# Sensors.net
KiCad netlist of a schematic drawn in Altium Designer
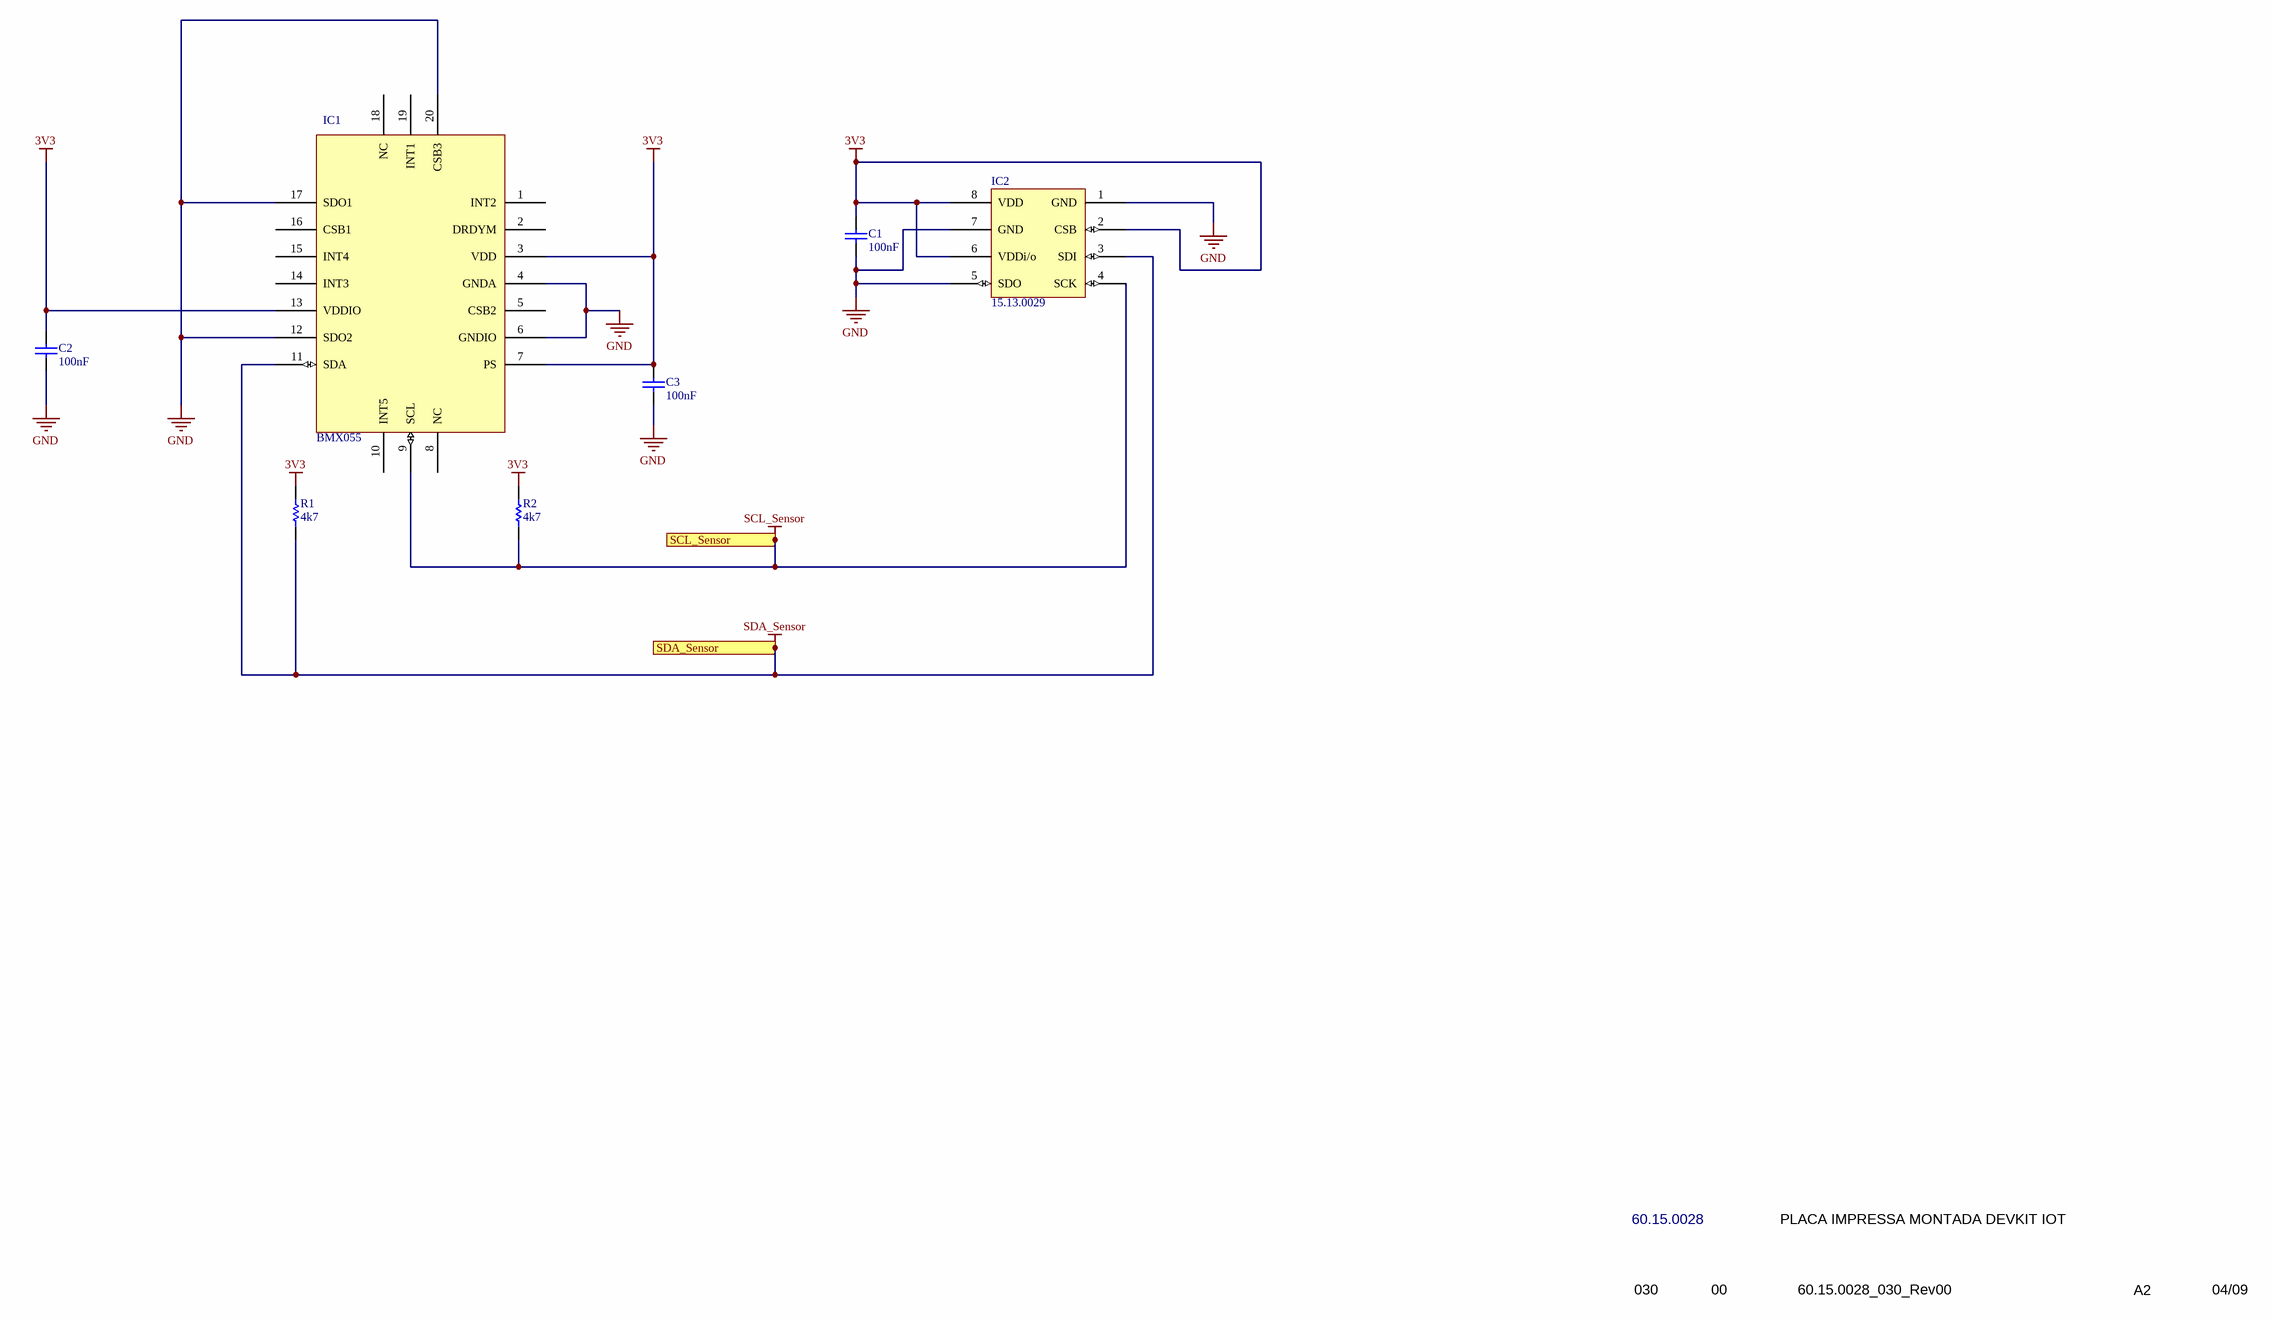
[diagram p0: Sensors.SchDoc]

(export (version "E")
  (design (tool "Eeschema 10.0.6"))
  (components
    (comp (ref "C1")
      (value "16.23.0333")
      (footprint "16.23.0333")
      (description "CC 100NF 16V X5R 0402 SMD")
      (fields (field (name "ALTIUM_UNNAMED_1") "100nF"))
      (libsource (lib "OMNI-CAPACITORES") (part "16.23.0333"))
    )
    (comp (ref "C2")
      (value "16.23.0333")
      (footprint "16.23.0333")
      (description "CC 100NF 16V X5R 0402 SMD")
      (fields (field (name "ALTIUM_UNNAMED_1") "100nF"))
      (libsource (lib "OMNI-CAPACITORES") (part "16.23.0333"))
    )
    (comp (ref "C3")
      (value "16.23.0333")
      (footprint "16.23.0333")
      (description "CC 100NF 16V X5R 0402 SMD")
      (fields (field (name "ALTIUM_UNNAMED_1") "100nF"))
      (libsource (lib "OMNI-CAPACITORES") (part "16.23.0333"))
    )
    (comp (ref "IC1")
      (value "BMX055")
      (footprint "15.15.0010")
      (description "SENSOR ACELEROMETRO MAGNETOMETRO E GIROSCOPIO - BMX055")
      (libsource (lib "OMNI-SENSORES") (part "15.15.0010"))
    )
    (comp (ref "IC2")
      (value "15.13.0029")
      (footprint "15.13.0029")
      (description "SENSOR DE TEMPERATURA UMIDADE E PRESSAO - BME280")
      (libsource (lib "OMNI-SENSORES") (part "15.13.0029"))
    )
    (comp (ref "R1")
      (value "4k7")
      (footprint "66.24.0659")
      (description "RES MET 0,1W 4,7K OHMS 1% 100 PPM 50 V SMD 0603 PBF")
      (fields (field (name "Comment") "66.24.0659"))
      (libsource (lib "OMNI-RESISTORES") (part "66.24.0659"))
    )
    (comp (ref "R2")
      (value "4k7")
      (footprint "66.24.0659")
      (description "RES MET 0,1W 4,7K OHMS 1% 100 PPM 50 V SMD 0603 PBF")
      (fields (field (name "Comment") "66.24.0659"))
      (libsource (lib "OMNI-RESISTORES") (part "66.24.0659"))
    )
  )
  (nets
    (net (code "1") (name "3V3") (class "Default")
      (node (ref "C1") (pin "2") (pinfunction "2_2") (pintype "passive"))
      (node (ref "C2") (pin "2") (pinfunction "2_2") (pintype "passive"))
      (node (ref "C3") (pin "2") (pinfunction "2_2") (pintype "passive"))
      (node (ref "IC1") (pin "13") (pinfunction "VDDIO_13") (pintype "power_in"))
      (node (ref "IC1") (pin "3") (pinfunction "VDD_3") (pintype "power_in"))
      (node (ref "IC1") (pin "7") (pinfunction "PS_7") (pintype "power_in"))
      (node (ref "IC2") (pin "2") (pinfunction "CSB_2") (pintype "bidirectional"))
      (node (ref "IC2") (pin "6") (pinfunction "VDDi/o_6") (pintype "power_in"))
      (node (ref "IC2") (pin "8") (pinfunction "VDD_8") (pintype "power_in"))
      (node (ref "R1") (pin "1") (pinfunction "1_1") (pintype "passive"))
      (node (ref "R2") (pin "1") (pinfunction "1_1") (pintype "passive"))
    )
    (net (code "2") (name "GND") (class "Default")
      (node (ref "C1") (pin "1") (pinfunction "1_1") (pintype "passive"))
      (node (ref "C2") (pin "1") (pinfunction "1_1") (pintype "passive"))
      (node (ref "C3") (pin "1") (pinfunction "1_1") (pintype "passive"))
      (node (ref "IC1") (pin "12") (pinfunction "SDO2_12") (pintype "passive"))
      (node (ref "IC1") (pin "17") (pinfunction "SDO1_17") (pintype "passive"))
      (node (ref "IC1") (pin "20") (pinfunction "CSB3_20") (pintype "passive"))
      (node (ref "IC1") (pin "4") (pinfunction "GNDA_4") (pintype "power_in"))
      (node (ref "IC1") (pin "6") (pinfunction "GNDIO_6") (pintype "power_in"))
      (node (ref "IC2") (pin "1") (pinfunction "GND_1") (pintype "power_in"))
      (node (ref "IC2") (pin "5") (pinfunction "SDO_5") (pintype "bidirectional"))
      (node (ref "IC2") (pin "7") (pinfunction "GND_7") (pintype "power_in"))
    )
    (net (code "3") (name "SCL_Sensor") (class "Default")
      (node (ref "IC1") (pin "9") (pinfunction "SCL_9") (pintype "bidirectional"))
      (node (ref "IC2") (pin "4") (pinfunction "SCK_4") (pintype "bidirectional"))
      (node (ref "R2") (pin "2") (pinfunction "2_2") (pintype "passive"))
    )
    (net (code "4") (name "SDA_Sensor") (class "Default")
      (node (ref "IC1") (pin "11") (pinfunction "SDA_11") (pintype "bidirectional"))
      (node (ref "IC2") (pin "3") (pinfunction "SDI_3") (pintype "bidirectional"))
      (node (ref "R1") (pin "2") (pinfunction "2_2") (pintype "passive"))
    )
    (net (code "5") (name "unconnected-(IC1-CSB1-Pad16)") (class "Default")
      (node (ref "IC1") (pin "16") (pinfunction "CSB1_16") (pintype "passive"))
    )
    (net (code "6") (name "unconnected-(IC1-CSB2-Pad5)") (class "Default")
      (node (ref "IC1") (pin "5") (pinfunction "CSB2_5") (pintype "passive"))
    )
    (net (code "7") (name "unconnected-(IC1-DRDYM-Pad2)") (class "Default")
      (node (ref "IC1") (pin "2") (pinfunction "DRDYM_2") (pintype "passive"))
    )
    (net (code "8") (name "unconnected-(IC1-INT1-Pad19)") (class "Default")
      (node (ref "IC1") (pin "19") (pinfunction "INT1_19") (pintype "passive"))
    )
    (net (code "9") (name "unconnected-(IC1-INT2-Pad1)") (class "Default")
      (node (ref "IC1") (pin "1") (pinfunction "INT2_1") (pintype "passive"))
    )
    (net (code "10") (name "unconnected-(IC1-INT3-Pad14)") (class "Default")
      (node (ref "IC1") (pin "14") (pinfunction "INT3_14") (pintype "passive"))
    )
    (net (code "11") (name "unconnected-(IC1-INT4-Pad15)") (class "Default")
      (node (ref "IC1") (pin "15") (pinfunction "INT4_15") (pintype "passive"))
    )
    (net (code "12") (name "unconnected-(IC1-INT5-Pad10)") (class "Default")
      (node (ref "IC1") (pin "10") (pinfunction "INT5_10") (pintype "passive"))
    )
    (net (code "13") (name "unconnected-(IC1-NC-Pad8)") (class "Default")
      (node (ref "IC1") (pin "8") (pinfunction "NC_8") (pintype "passive"))
    )
    (net (code "14") (name "unconnected-(IC1-NC-Pad18)") (class "Default")
      (node (ref "IC1") (pin "18") (pinfunction "NC_18") (pintype "passive"))
    )
  )
)
